# Occupancy_PCB.net
KiCad netlist of a schematic drawn in EAGLE
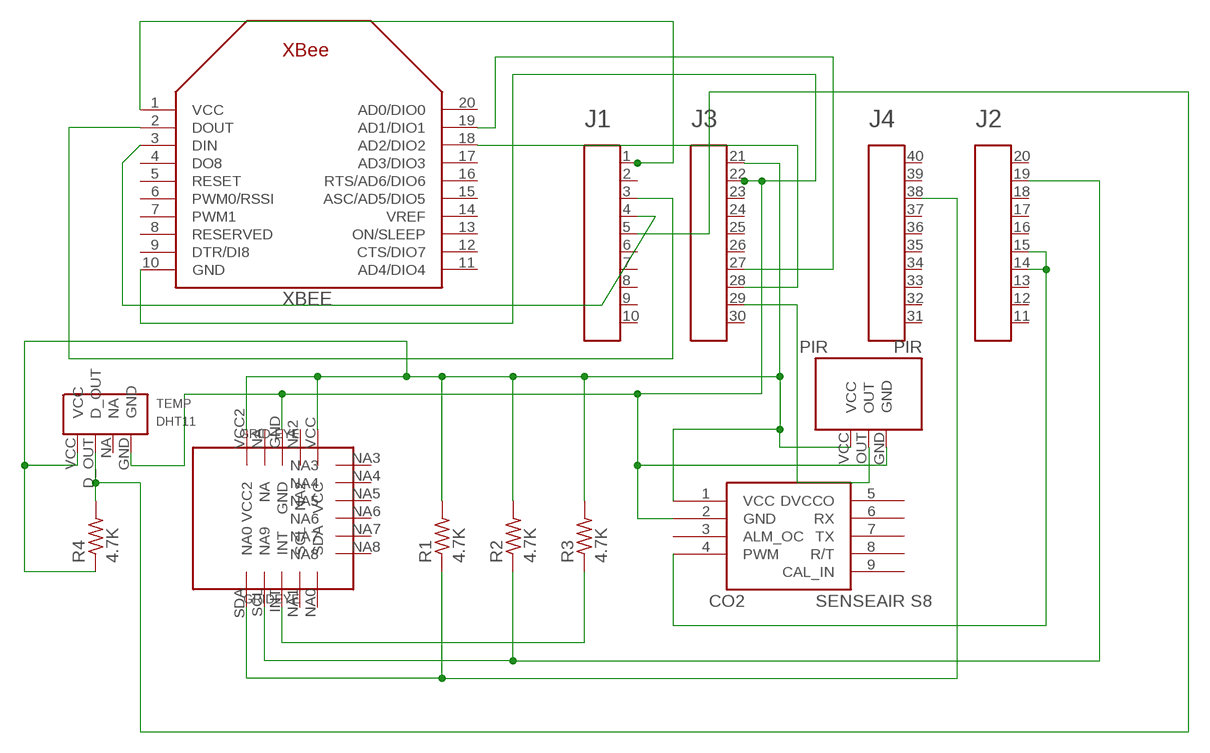
[diagram p0: schematic, sheet 1]

(export (version "E")
  (design (tool "Eeschema 10.0.6"))
  (components
    (comp (ref "CO2")
      (value "SENSEAIR-S8-DIP")
      (footprint "eagle-import:SENSEAIR-S8-DIP")
      (libsource (lib "eagle-import") (part "SENSEAIR-S8-DIP"))
    )
    (comp (ref "GRIDEYE")
      (value "GRID-EYE-DIP")
      (footprint "eagle-import:GRID-EYE-DIP")
      (libsource (lib "eagle-import") (part "GRID-EYE-DIP"))
    )
    (comp (ref "LAUNCHPAD")
      (value "HEADER4X10-BOOSTERPACK")
      (footprint "eagle-import:4X10-BOOSTERPACK")
      (libsource (lib "eagle-import") (part "HEADER4X10-BOOSTERPACK"))
    )
    (comp (ref "PIR")
      (value "PIR-DIP")
      (footprint "eagle-import:PIR-DIP")
      (libsource (lib "eagle-import") (part "PIR-DIP"))
    )
    (comp (ref "R1")
      (value "4.7K")
      (footprint "eagle-import:R0805")
      (libsource (lib "eagle-import") (part "R-US_R0805"))
    )
    (comp (ref "R2")
      (value "4.7K")
      (footprint "eagle-import:R0805")
      (libsource (lib "eagle-import") (part "R-US_R0805"))
    )
    (comp (ref "R3")
      (value "4.7K")
      (footprint "eagle-import:R0805")
      (libsource (lib "eagle-import") (part "R-US_R0805"))
    )
    (comp (ref "R4")
      (value "4.7K")
      (footprint "eagle-import:R0805")
      (libsource (lib "eagle-import") (part "R-US_R0805"))
    )
    (comp (ref "TEMP")
      (value "DHT11-DIP")
      (footprint "eagle-import:DHT11-DIP")
      (libsource (lib "eagle-import") (part "DHT11-DIP"))
    )
    (comp (ref "XBEE")
      (value "XBEE")
      (footprint "eagle-import:XBEE")
      (libsource (lib "eagle-import") (part "XBEE"))
    )
  )
  (nets
    (net (code "1") (name "Net-(CO2-GND)") (class "Default")
      (node (ref "CO2") (pin "2") (pinfunction "GND_2") (pintype "bidirectional"))
      (node (ref "GRIDEYE") (pin "GND") (pinfunction "GND_GND") (pintype "bidirectional"))
      (node (ref "LAUNCHPAD") (pin "22") (pinfunction "P$22_22") (pintype "bidirectional"))
      (node (ref "PIR") (pin "GND") (pinfunction "GND_GND") (pintype "bidirectional"))
      (node (ref "TEMP") (pin "GND") (pinfunction "GND_GND") (pintype "bidirectional"))
      (node (ref "XBEE") (pin "10") (pinfunction "GND_10") (pintype "power_in"))
    )
    (net (code "2") (name "Net-(CO2-PWM)") (class "Default")
      (node (ref "CO2") (pin "4") (pinfunction "PWM_4") (pintype "bidirectional"))
      (node (ref "LAUNCHPAD") (pin "14") (pinfunction "P$14_14") (pintype "bidirectional"))
      (node (ref "LAUNCHPAD") (pin "15") (pinfunction "P$15_15") (pintype "bidirectional"))
    )
    (net (code "3") (name "Net-(CO2-VCC)") (class "Default")
      (node (ref "CO2") (pin "1") (pinfunction "VCC_1") (pintype "bidirectional"))
      (node (ref "GRIDEYE") (pin "VCC") (pinfunction "VCC_VCC") (pintype "bidirectional"))
      (node (ref "GRIDEYE") (pin "VCC2") (pinfunction "VCC2_VCC2") (pintype "bidirectional"))
      (node (ref "LAUNCHPAD") (pin "21") (pinfunction "P$21_21") (pintype "bidirectional"))
      (node (ref "PIR") (pin "VCC") (pinfunction "VCC_VCC") (pintype "bidirectional"))
      (node (ref "R1") (pin "2") (pinfunction "2_2") (pintype "passive"))
      (node (ref "R2") (pin "2") (pinfunction "2_2") (pintype "passive"))
      (node (ref "R3") (pin "2") (pinfunction "2_2") (pintype "passive"))
      (node (ref "R4") (pin "1") (pinfunction "1_1") (pintype "passive"))
      (node (ref "TEMP") (pin "VCC") (pinfunction "VCC_VCC") (pintype "bidirectional"))
    )
    (net (code "4") (name "Net-(GRIDEYE-NA0)") (class "Default")
      (node (ref "GRIDEYE") (pin "SDA") (pinfunction "NA0_SDA") (pintype "bidirectional"))
      (node (ref "LAUNCHPAD") (pin "38") (pinfunction "P$38_38") (pintype "bidirectional"))
      (node (ref "R1") (pin "1") (pinfunction "1_1") (pintype "passive"))
    )
    (net (code "5") (name "Net-(GRIDEYE-NA9)") (class "Default")
      (node (ref "GRIDEYE") (pin "SCL") (pinfunction "NA9_SCL") (pintype "bidirectional"))
      (node (ref "LAUNCHPAD") (pin "19") (pinfunction "P$19_19") (pintype "bidirectional"))
      (node (ref "R2") (pin "1") (pinfunction "1_1") (pintype "passive"))
    )
    (net (code "6") (name "Net-(GRIDEYE-PadINT)") (class "Default")
      (node (ref "GRIDEYE") (pin "INT") (pinfunction "INT_INT") (pintype "bidirectional"))
      (node (ref "R3") (pin "1") (pinfunction "1_1") (pintype "passive"))
    )
    (net (code "7") (name "Net-(LAUNCHPAD-P$1)") (class "Default")
      (node (ref "LAUNCHPAD") (pin "1") (pinfunction "P$1_1") (pintype "bidirectional"))
      (node (ref "XBEE") (pin "1") (pinfunction "VCC_1") (pintype "power_in"))
    )
    (net (code "8") (name "Net-(LAUNCHPAD-P$3)") (class "Default")
      (node (ref "LAUNCHPAD") (pin "3") (pinfunction "P$3_3") (pintype "bidirectional"))
      (node (ref "XBEE") (pin "2") (pinfunction "DOUT_2") (pintype "output"))
    )
    (net (code "9") (name "Net-(LAUNCHPAD-P$4)") (class "Default")
      (node (ref "LAUNCHPAD") (pin "4") (pinfunction "P$4_4") (pintype "bidirectional"))
      (node (ref "XBEE") (pin "3") (pinfunction "DIN_3") (pintype "input"))
    )
    (net (code "10") (name "Net-(LAUNCHPAD-P$5)") (class "Default")
      (node (ref "LAUNCHPAD") (pin "5") (pinfunction "P$5_5") (pintype "bidirectional"))
      (node (ref "R4") (pin "2") (pinfunction "2_2") (pintype "passive"))
      (node (ref "TEMP") (pin "D_OUT") (pinfunction "D_OUT_D_OUT") (pintype "bidirectional"))
    )
    (net (code "11") (name "Net-(LAUNCHPAD-P$27)") (class "Default")
      (node (ref "LAUNCHPAD") (pin "27") (pinfunction "P$27_27") (pintype "bidirectional"))
      (node (ref "XBEE") (pin "19") (pinfunction "AD1/DIO1_19") (pintype "bidirectional"))
    )
    (net (code "12") (name "Net-(LAUNCHPAD-P$28)") (class "Default")
      (node (ref "LAUNCHPAD") (pin "28") (pinfunction "P$28_28") (pintype "bidirectional"))
      (node (ref "XBEE") (pin "18") (pinfunction "AD2/DIO2_18") (pintype "bidirectional"))
    )
    (net (code "13") (name "Net-(LAUNCHPAD-P$29)") (class "Default")
      (node (ref "LAUNCHPAD") (pin "29") (pinfunction "P$29_29") (pintype "bidirectional"))
      (node (ref "PIR") (pin "OUT") (pinfunction "OUT_OUT") (pintype "bidirectional"))
    )
    (net (code "14") (name "unconnected-(CO2-ALM_OC-Pad3)") (class "Default")
      (node (ref "CO2") (pin "3") (pinfunction "ALM_OC_3") (pintype "bidirectional"))
    )
    (net (code "15") (name "unconnected-(CO2-CAL_IN-Pad9)") (class "Default")
      (node (ref "CO2") (pin "9") (pinfunction "CAL_IN_9") (pintype "bidirectional"))
    )
    (net (code "16") (name "unconnected-(CO2-DVCCO-Pad5)") (class "Default")
      (node (ref "CO2") (pin "5") (pinfunction "DVCCO_5") (pintype "bidirectional"))
    )
    (net (code "17") (name "unconnected-(CO2-RX-Pad6)") (class "Default")
      (node (ref "CO2") (pin "6") (pinfunction "RX_6") (pintype "bidirectional"))
    )
    (net (code "18") (name "unconnected-(CO2-R{slash}T-Pad8)") (class "Default")
      (node (ref "CO2") (pin "8") (pinfunction "R/T_8") (pintype "bidirectional"))
    )
    (net (code "19") (name "unconnected-(CO2-TX-Pad7)") (class "Default")
      (node (ref "CO2") (pin "7") (pinfunction "TX_7") (pintype "bidirectional"))
    )
    (net (code "20") (name "unconnected-(GRIDEYE-PadNA)") (class "Default")
      (node (ref "GRIDEYE") (pin "NA") (pinfunction "NA_NA") (pintype "bidirectional"))
    )
    (net (code "21") (name "unconnected-(GRIDEYE-PadNA2)") (class "Default")
      (node (ref "GRIDEYE") (pin "NA2") (pinfunction "NA2_NA2") (pintype "bidirectional"))
    )
    (net (code "22") (name "unconnected-(GRIDEYE-PadNA3)") (class "Default")
      (node (ref "GRIDEYE") (pin "NA3") (pinfunction "NA3_NA3") (pintype "bidirectional"))
    )
    (net (code "23") (name "unconnected-(GRIDEYE-PadNA4)") (class "Default")
      (node (ref "GRIDEYE") (pin "NA4") (pinfunction "NA4_NA4") (pintype "bidirectional"))
    )
    (net (code "24") (name "unconnected-(GRIDEYE-PadNA5)") (class "Default")
      (node (ref "GRIDEYE") (pin "NA5") (pinfunction "NA5_NA5") (pintype "bidirectional"))
    )
    (net (code "25") (name "unconnected-(GRIDEYE-PadNA6)") (class "Default")
      (node (ref "GRIDEYE") (pin "NA6") (pinfunction "NA6_NA6") (pintype "bidirectional"))
    )
    (net (code "26") (name "unconnected-(GRIDEYE-PadNA7)") (class "Default")
      (node (ref "GRIDEYE") (pin "NA7") (pinfunction "NA7_NA7") (pintype "bidirectional"))
    )
    (net (code "27") (name "unconnected-(GRIDEYE-PadNA8)") (class "Default")
      (node (ref "GRIDEYE") (pin "NA8") (pinfunction "NA8_NA8") (pintype "bidirectional"))
    )
    (net (code "28") (name "unconnected-(GRIDEYE-SCL-PadNA1)") (class "Default")
      (node (ref "GRIDEYE") (pin "NA1") (pinfunction "SCL_NA1") (pintype "bidirectional"))
    )
    (net (code "29") (name "unconnected-(GRIDEYE-SDA-PadNA0)") (class "Default")
      (node (ref "GRIDEYE") (pin "NA0") (pinfunction "SDA_NA0") (pintype "bidirectional"))
    )
    (net (code "30") (name "unconnected-(LAUNCHPAD-P$2-Pad2)") (class "Default")
      (node (ref "LAUNCHPAD") (pin "2") (pinfunction "P$2_2") (pintype "bidirectional"))
    )
    (net (code "31") (name "unconnected-(LAUNCHPAD-P$6-Pad6)") (class "Default")
      (node (ref "LAUNCHPAD") (pin "6") (pinfunction "P$6_6") (pintype "bidirectional"))
    )
    (net (code "32") (name "unconnected-(LAUNCHPAD-P$7-Pad7)") (class "Default")
      (node (ref "LAUNCHPAD") (pin "7") (pinfunction "P$7_7") (pintype "bidirectional"))
    )
    (net (code "33") (name "unconnected-(LAUNCHPAD-P$8-Pad8)") (class "Default")
      (node (ref "LAUNCHPAD") (pin "8") (pinfunction "P$8_8") (pintype "bidirectional"))
    )
    (net (code "34") (name "unconnected-(LAUNCHPAD-P$9-Pad9)") (class "Default")
      (node (ref "LAUNCHPAD") (pin "9") (pinfunction "P$9_9") (pintype "bidirectional"))
    )
    (net (code "35") (name "unconnected-(LAUNCHPAD-P$10-Pad10)") (class "Default")
      (node (ref "LAUNCHPAD") (pin "10") (pinfunction "P$10_10") (pintype "bidirectional"))
    )
    (net (code "36") (name "unconnected-(LAUNCHPAD-P$11-Pad11)") (class "Default")
      (node (ref "LAUNCHPAD") (pin "11") (pinfunction "P$11_11") (pintype "bidirectional"))
    )
    (net (code "37") (name "unconnected-(LAUNCHPAD-P$12-Pad12)") (class "Default")
      (node (ref "LAUNCHPAD") (pin "12") (pinfunction "P$12_12") (pintype "bidirectional"))
    )
    (net (code "38") (name "unconnected-(LAUNCHPAD-P$13-Pad13)") (class "Default")
      (node (ref "LAUNCHPAD") (pin "13") (pinfunction "P$13_13") (pintype "bidirectional"))
    )
    (net (code "39") (name "unconnected-(LAUNCHPAD-P$16-Pad16)") (class "Default")
      (node (ref "LAUNCHPAD") (pin "16") (pinfunction "P$16_16") (pintype "bidirectional"))
    )
    (net (code "40") (name "unconnected-(LAUNCHPAD-P$17-Pad17)") (class "Default")
      (node (ref "LAUNCHPAD") (pin "17") (pinfunction "P$17_17") (pintype "bidirectional"))
    )
    (net (code "41") (name "unconnected-(LAUNCHPAD-P$18-Pad18)") (class "Default")
      (node (ref "LAUNCHPAD") (pin "18") (pinfunction "P$18_18") (pintype "bidirectional"))
    )
    (net (code "42") (name "unconnected-(LAUNCHPAD-P$20-Pad20)") (class "Default")
      (node (ref "LAUNCHPAD") (pin "20") (pinfunction "P$20_20") (pintype "bidirectional"))
    )
    (net (code "43") (name "unconnected-(LAUNCHPAD-P$23-Pad23)") (class "Default")
      (node (ref "LAUNCHPAD") (pin "23") (pinfunction "P$23_23") (pintype "bidirectional"))
    )
    (net (code "44") (name "unconnected-(LAUNCHPAD-P$24-Pad24)") (class "Default")
      (node (ref "LAUNCHPAD") (pin "24") (pinfunction "P$24_24") (pintype "bidirectional"))
    )
    (net (code "45") (name "unconnected-(LAUNCHPAD-P$25-Pad25)") (class "Default")
      (node (ref "LAUNCHPAD") (pin "25") (pinfunction "P$25_25") (pintype "bidirectional"))
    )
    (net (code "46") (name "unconnected-(LAUNCHPAD-P$26-Pad26)") (class "Default")
      (node (ref "LAUNCHPAD") (pin "26") (pinfunction "P$26_26") (pintype "bidirectional"))
    )
    (net (code "47") (name "unconnected-(LAUNCHPAD-P$30-Pad30)") (class "Default")
      (node (ref "LAUNCHPAD") (pin "30") (pinfunction "P$30_30") (pintype "bidirectional"))
    )
    (net (code "48") (name "unconnected-(LAUNCHPAD-P$31-Pad31)") (class "Default")
      (node (ref "LAUNCHPAD") (pin "31") (pinfunction "P$31_31") (pintype "bidirectional"))
    )
    (net (code "49") (name "unconnected-(LAUNCHPAD-P$32-Pad32)") (class "Default")
      (node (ref "LAUNCHPAD") (pin "32") (pinfunction "P$32_32") (pintype "bidirectional"))
    )
    (net (code "50") (name "unconnected-(LAUNCHPAD-P$33-Pad33)") (class "Default")
      (node (ref "LAUNCHPAD") (pin "33") (pinfunction "P$33_33") (pintype "bidirectional"))
    )
    (net (code "51") (name "unconnected-(LAUNCHPAD-P$34-Pad34)") (class "Default")
      (node (ref "LAUNCHPAD") (pin "34") (pinfunction "P$34_34") (pintype "bidirectional"))
    )
    (net (code "52") (name "unconnected-(LAUNCHPAD-P$35-Pad35)") (class "Default")
      (node (ref "LAUNCHPAD") (pin "35") (pinfunction "P$35_35") (pintype "bidirectional"))
    )
    (net (code "53") (name "unconnected-(LAUNCHPAD-P$36-Pad36)") (class "Default")
      (node (ref "LAUNCHPAD") (pin "36") (pinfunction "P$36_36") (pintype "bidirectional"))
    )
    (net (code "54") (name "unconnected-(LAUNCHPAD-P$37-Pad37)") (class "Default")
      (node (ref "LAUNCHPAD") (pin "37") (pinfunction "P$37_37") (pintype "bidirectional"))
    )
    (net (code "55") (name "unconnected-(LAUNCHPAD-P$39-Pad39)") (class "Default")
      (node (ref "LAUNCHPAD") (pin "39") (pinfunction "P$39_39") (pintype "bidirectional"))
    )
    (net (code "56") (name "unconnected-(LAUNCHPAD-P$40-Pad40)") (class "Default")
      (node (ref "LAUNCHPAD") (pin "40") (pinfunction "P$40_40") (pintype "bidirectional"))
    )
    (net (code "57") (name "unconnected-(TEMP-PadNA)") (class "Default")
      (node (ref "TEMP") (pin "NA") (pinfunction "NA_NA") (pintype "bidirectional"))
    )
    (net (code "58") (name "unconnected-(XBEE-AD0{slash}DIO0-Pad20)") (class "Default")
      (node (ref "XBEE") (pin "20") (pinfunction "AD0/DIO0_20") (pintype "bidirectional"))
    )
    (net (code "59") (name "unconnected-(XBEE-AD3{slash}DIO3-Pad17)") (class "Default")
      (node (ref "XBEE") (pin "17") (pinfunction "AD3/DIO3_17") (pintype "bidirectional"))
    )
    (net (code "60") (name "unconnected-(XBEE-AD4{slash}DIO4-Pad11)") (class "Default")
      (node (ref "XBEE") (pin "11") (pinfunction "AD4/DIO4_11") (pintype "bidirectional"))
    )
    (net (code "61") (name "unconnected-(XBEE-ASC{slash}AD5{slash}DIO5-Pad15)") (class "Default")
      (node (ref "XBEE") (pin "15") (pinfunction "ASC/AD5/DIO5_15") (pintype "bidirectional"))
    )
    (net (code "62") (name "unconnected-(XBEE-CTS{slash}DIO7-Pad12)") (class "Default")
      (node (ref "XBEE") (pin "12") (pinfunction "CTS/DIO7_12") (pintype "bidirectional"))
    )
    (net (code "63") (name "unconnected-(XBEE-DO8-Pad4)") (class "Default")
      (node (ref "XBEE") (pin "4") (pinfunction "DO8_4") (pintype "output"))
    )
    (net (code "64") (name "unconnected-(XBEE-DTR{slash}DI8-Pad9)") (class "Default")
      (node (ref "XBEE") (pin "9") (pinfunction "DTR/DI8_9") (pintype "input"))
    )
    (net (code "65") (name "unconnected-(XBEE-ON{slash}SLEEP-Pad13)") (class "Default")
      (node (ref "XBEE") (pin "13") (pinfunction "ON/SLEEP_13") (pintype "output"))
    )
    (net (code "66") (name "unconnected-(XBEE-PWM0{slash}RSSI-Pad6)") (class "Default")
      (node (ref "XBEE") (pin "6") (pinfunction "PWM0/RSSI_6") (pintype "output"))
    )
    (net (code "67") (name "unconnected-(XBEE-PWM1-Pad7)") (class "Default")
      (node (ref "XBEE") (pin "7") (pinfunction "PWM1_7") (pintype "output"))
    )
    (net (code "68") (name "unconnected-(XBEE-RESERVED-Pad8)") (class "Default")
      (node (ref "XBEE") (pin "8") (pinfunction "RESERVED_8") (pintype "no_connect"))
    )
    (net (code "69") (name "unconnected-(XBEE-RESET-Pad5)") (class "Default")
      (node (ref "XBEE") (pin "5") (pinfunction "RESET_5") (pintype "input"))
    )
    (net (code "70") (name "unconnected-(XBEE-RTS{slash}AD6{slash}DIO6-Pad16)") (class "Default")
      (node (ref "XBEE") (pin "16") (pinfunction "RTS/AD6/DIO6_16") (pintype "bidirectional"))
    )
    (net (code "71") (name "unconnected-(XBEE-VREF-Pad14)") (class "Default")
      (node (ref "XBEE") (pin "14") (pinfunction "VREF_14") (pintype "input"))
    )
  )
)
